# sensor.net
KiCad netlist of a schematic drawn in Altium Designer
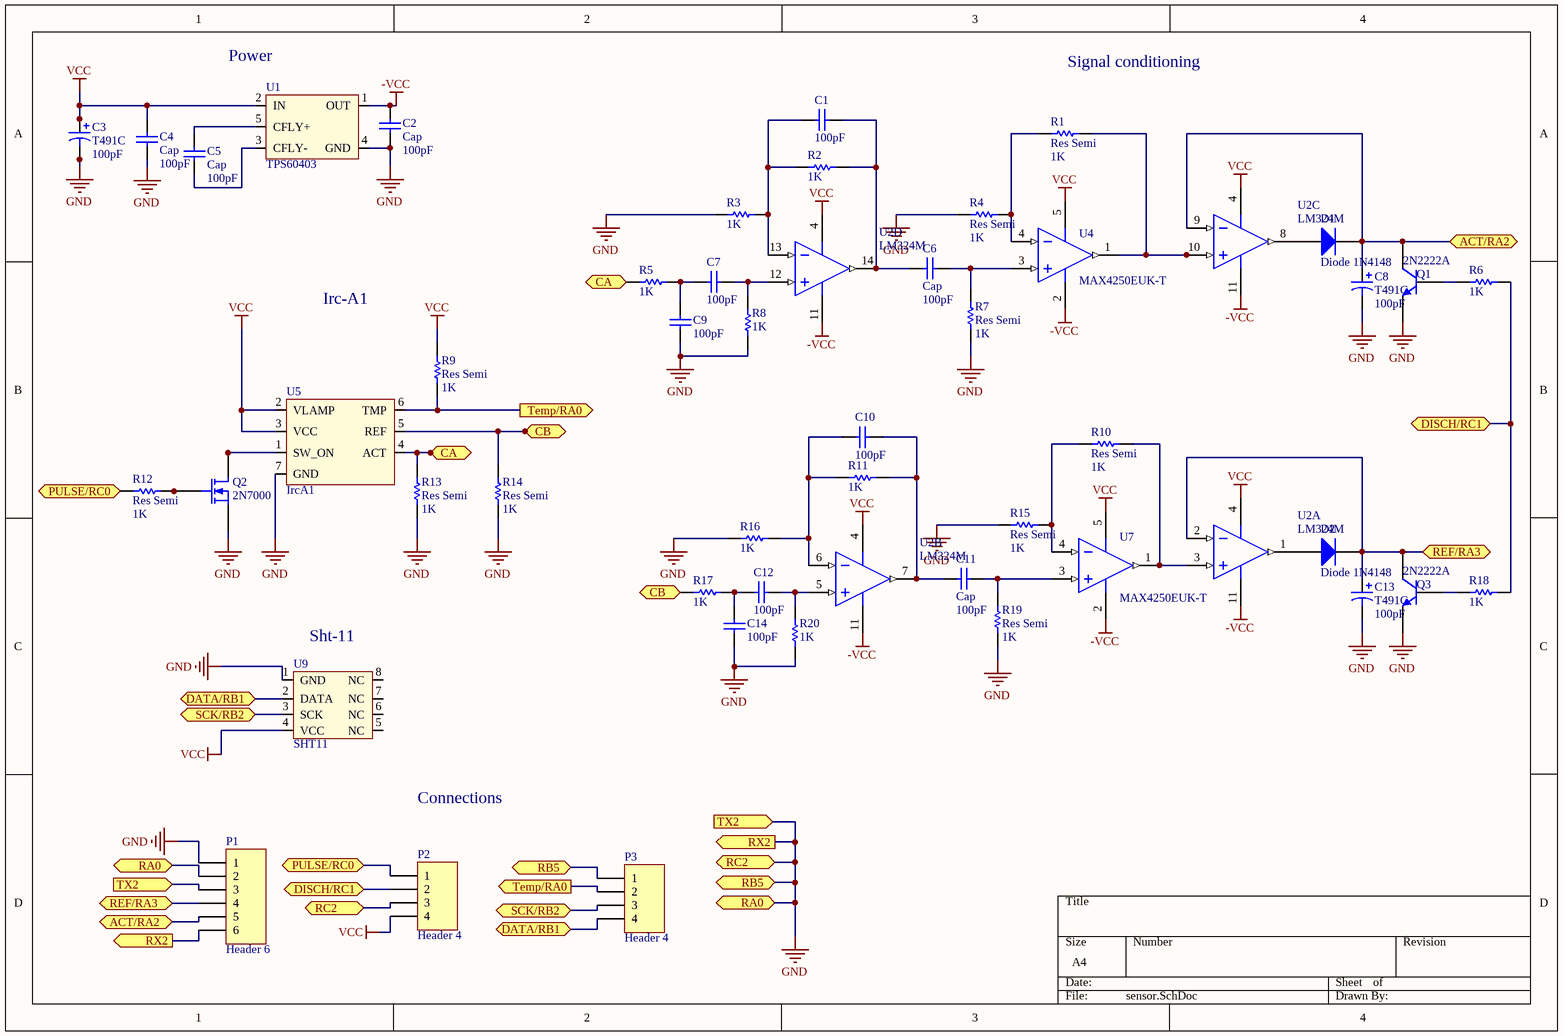
[diagram p0: sensor.SchDoc]

(export (version "E")
  (design (tool "Eeschema 10.0.6"))
  (components
    (comp (ref "C1")
      (value "100pF")
      (footprint "C1206")
      (description "Capacitor")
      (fields (field (name "Comment") "Cap") (field (name "PUBLISHER") "Altium Limited"))
      (libsource (lib "Miscellaneous Devices") (part "Cap"))
    )
    (comp (ref "C2")
      (value "Cap")
      (footprint "C1206")
      (description "Capacitor")
      (fields (field (name "ALTIUM_VALUE") "100pF") (field (name "PUBLISHER") "Altium Limited"))
      (libsource (lib "Miscellaneous Devices") (part "Cap"))
    )
    (comp (ref "C3")
      (value "T491C")
      (footprint "C")
      (description "Solid Tantalum Chip Capacitor, Standard T491 Series - Industrial Grade")
      (fields (field (name "ALTIUM_VALUE") "100pF") (field (name "PUBLISHER") "Altium Limited"))
      (libsource (lib "KEMET Chip Capacitor") (part "T491C"))
    )
    (comp (ref "C4")
      (value "Cap")
      (footprint "C1206")
      (description "Capacitor")
      (fields (field (name "ALTIUM_VALUE") "100pF") (field (name "PUBLISHER") "Altium Limited"))
      (libsource (lib "Miscellaneous Devices") (part "Cap"))
    )
    (comp (ref "C5")
      (value "Cap")
      (footprint "C1206")
      (description "Capacitor")
      (fields (field (name "ALTIUM_VALUE") "100pF") (field (name "PUBLISHER") "Altium Limited"))
      (libsource (lib "Miscellaneous Devices") (part "Cap"))
    )
    (comp (ref "C6")
      (value "Cap")
      (footprint "C1206")
      (description "Capacitor")
      (fields (field (name "ALTIUM_VALUE") "100pF") (field (name "PUBLISHER") "Altium Limited"))
      (libsource (lib "Miscellaneous Devices") (part "Cap"))
    )
    (comp (ref "C7")
      (value "100pF")
      (footprint "C1206")
      (description "Capacitor")
      (fields (field (name "Comment") "Cap") (field (name "PUBLISHER") "Altium Limited"))
      (libsource (lib "Miscellaneous Devices") (part "Cap"))
    )
    (comp (ref "C8")
      (value "T491C")
      (footprint "C")
      (description "Solid Tantalum Chip Capacitor, Standard T491 Series - Industrial Grade")
      (fields (field (name "ALTIUM_VALUE") "100pF") (field (name "PUBLISHER") "Altium Limited"))
      (libsource (lib "KEMET Chip Capacitor") (part "T491C"))
    )
    (comp (ref "C9")
      (value "100pF")
      (footprint "C1206")
      (description "Capacitor")
      (fields (field (name "Comment") "Cap") (field (name "PUBLISHER") "Altium Limited"))
      (libsource (lib "Miscellaneous Devices") (part "Cap"))
    )
    (comp (ref "C10")
      (value "100pF")
      (footprint "C1206")
      (description "Capacitor")
      (fields (field (name "Comment") "Cap") (field (name "PUBLISHER") "Altium Limited"))
      (libsource (lib "Miscellaneous Devices") (part "Cap"))
    )
    (comp (ref "C11")
      (value "Cap")
      (footprint "C1206")
      (description "Capacitor")
      (fields (field (name "ALTIUM_VALUE") "100pF") (field (name "PUBLISHER") "Altium Limited"))
      (libsource (lib "Miscellaneous Devices") (part "Cap"))
    )
    (comp (ref "C12")
      (value "100pF")
      (footprint "C1206")
      (description "Capacitor")
      (fields (field (name "Comment") "Cap") (field (name "PUBLISHER") "Altium Limited"))
      (libsource (lib "Miscellaneous Devices") (part "Cap"))
    )
    (comp (ref "C13")
      (value "T491C")
      (footprint "C")
      (description "Solid Tantalum Chip Capacitor, Standard T491 Series - Industrial Grade")
      (fields (field (name "ALTIUM_VALUE") "100pF") (field (name "PUBLISHER") "Altium Limited"))
      (libsource (lib "KEMET Chip Capacitor") (part "T491C"))
    )
    (comp (ref "C14")
      (value "100pF")
      (footprint "C1206")
      (description "Capacitor")
      (fields (field (name "Comment") "Cap") (field (name "PUBLISHER") "Altium Limited"))
      (libsource (lib "Miscellaneous Devices") (part "Cap"))
    )
    (comp (ref "D1")
      (value "Diode 1N4148")
      (footprint "LED SMD 1206")
      (description "High Conductance Fast Diode")
      (fields (field (name "PUBLISHER") "Altium Limited"))
      (libsource (lib "Miscellaneous Devices") (part "Diode 1N4148"))
    )
    (comp (ref "D2")
      (value "Diode 1N4148")
      (footprint "LED SMD 1206")
      (description "High Conductance Fast Diode")
      (fields (field (name "PUBLISHER") "Altium Limited"))
      (libsource (lib "Miscellaneous Devices") (part "Diode 1N4148"))
    )
    (comp (ref "P1")
      (value "Header 6")
      (footprint "HDR1X6")
      (description "Header, 6-Pin")
      (fields (field (name "PUBLISHER") "Altium Limited"))
      (libsource (lib "Miscellaneous Connectors") (part "Header 6"))
    )
    (comp (ref "P2")
      (value "Header 4")
      (footprint "HDR1X4")
      (description "Header, 4-Pin")
      (fields (field (name "PUBLISHER") "Altium Limited"))
      (libsource (lib "Miscellaneous Connectors") (part "Header 4"))
    )
    (comp (ref "P3")
      (value "Header 4")
      (footprint "HDR1X4")
      (description "Header, 4-Pin")
      (fields (field (name "PUBLISHER") "Altium Limited"))
      (libsource (lib "Miscellaneous Connectors") (part "Header 4"))
    )
    (comp (ref "Q1")
      (value "2N2222A")
      (footprint "SOT323-3BM")
      (description "High Speed Switches")
      (fields (field (name "PUBLISHER") "Altium Limited"))
      (libsource (lib "ST Discrete BJT") (part "2N2222A"))
    )
    (comp (ref "Q2")
      (value "2N7000")
      (footprint "SOT23-3L")
      (description "N-Channel Enhancement Mode Vertical DMOS FET")
      (fields (field (name "PUBLISHER") "Altium Limited"))
      (libsource (lib "Zetex Discrete MOSFET") (part "2N7000"))
    )
    (comp (ref "Q3")
      (value "2N2222A")
      (footprint "SOT323-3BM")
      (description "High Speed Switches")
      (fields (field (name "PUBLISHER") "Altium Limited"))
      (libsource (lib "ST Discrete BJT") (part "2N2222A"))
    )
    (comp (ref "R1")
      (value "Res Semi")
      (footprint "3216[1206]")
      (description "Semiconductor Resistor")
      (fields (field (name "ALTIUM_VALUE") "1K") (field (name "PUBLISHER") "Altium Limited"))
      (libsource (lib "Miscellaneous Devices") (part "Res Semi"))
    )
    (comp (ref "R2")
      (value "1K")
      (footprint "3216[1206]")
      (description "Semiconductor Resistor")
      (fields (field (name "Comment") "Res Semi") (field (name "PUBLISHER") "Altium Limited"))
      (libsource (lib "Miscellaneous Devices") (part "Res Semi"))
    )
    (comp (ref "R3")
      (value "1K")
      (footprint "3216[1206]")
      (description "Semiconductor Resistor")
      (fields (field (name "Comment") "Res Semi") (field (name "PUBLISHER") "Altium Limited"))
      (libsource (lib "Miscellaneous Devices") (part "Res Semi"))
    )
    (comp (ref "R4")
      (value "Res Semi")
      (footprint "3216[1206]")
      (description "Semiconductor Resistor")
      (fields (field (name "ALTIUM_VALUE") "1K") (field (name "PUBLISHER") "Altium Limited"))
      (libsource (lib "Miscellaneous Devices") (part "Res Semi"))
    )
    (comp (ref "R5")
      (value "1K")
      (footprint "3216[1206]")
      (description "Semiconductor Resistor")
      (fields (field (name "Comment") "Res Semi") (field (name "PUBLISHER") "Altium Limited"))
      (libsource (lib "Miscellaneous Devices") (part "Res Semi"))
    )
    (comp (ref "R6")
      (value "1K")
      (footprint "3216[1206]")
      (description "Semiconductor Resistor")
      (fields (field (name "Comment") "Res Semi") (field (name "PUBLISHER") "Altium Limited"))
      (libsource (lib "Miscellaneous Devices") (part "Res Semi"))
    )
    (comp (ref "R7")
      (value "Res Semi")
      (footprint "3216[1206]")
      (description "Semiconductor Resistor")
      (fields (field (name "ALTIUM_VALUE") "1K") (field (name "PUBLISHER") "Altium Limited"))
      (libsource (lib "Miscellaneous Devices") (part "Res Semi"))
    )
    (comp (ref "R8")
      (value "1K")
      (footprint "3216[1206]")
      (description "Semiconductor Resistor")
      (fields (field (name "Comment") "Res Semi") (field (name "PUBLISHER") "Altium Limited"))
      (libsource (lib "Miscellaneous Devices") (part "Res Semi"))
    )
    (comp (ref "R9")
      (value "Res Semi")
      (footprint "3216[1206]")
      (description "Semiconductor Resistor")
      (fields (field (name "ALTIUM_VALUE") "1K") (field (name "PUBLISHER") "Altium Limited"))
      (libsource (lib "Miscellaneous Devices") (part "Res Semi"))
    )
    (comp (ref "R10")
      (value "Res Semi")
      (footprint "3216[1206]")
      (description "Semiconductor Resistor")
      (fields (field (name "ALTIUM_VALUE") "1K") (field (name "PUBLISHER") "Altium Limited"))
      (libsource (lib "Miscellaneous Devices") (part "Res Semi"))
    )
    (comp (ref "R11")
      (value "1K")
      (footprint "3216[1206]")
      (description "Semiconductor Resistor")
      (fields (field (name "Comment") "Res Semi") (field (name "PUBLISHER") "Altium Limited"))
      (libsource (lib "Miscellaneous Devices") (part "Res Semi"))
    )
    (comp (ref "R12")
      (value "Res Semi")
      (footprint "3216[1206]")
      (description "Semiconductor Resistor")
      (fields (field (name "ALTIUM_VALUE") "1K") (field (name "PUBLISHER") "Altium Limited"))
      (libsource (lib "Miscellaneous Devices") (part "Res Semi"))
    )
    (comp (ref "R13")
      (value "Res Semi")
      (footprint "3216[1206]")
      (description "Semiconductor Resistor")
      (fields (field (name "ALTIUM_VALUE") "1K") (field (name "PUBLISHER") "Altium Limited"))
      (libsource (lib "Miscellaneous Devices") (part "Res Semi"))
    )
    (comp (ref "R14")
      (value "Res Semi")
      (footprint "3216[1206]")
      (description "Semiconductor Resistor")
      (fields (field (name "ALTIUM_VALUE") "1K") (field (name "PUBLISHER") "Altium Limited"))
      (libsource (lib "Miscellaneous Devices") (part "Res Semi"))
    )
    (comp (ref "R15")
      (value "Res Semi")
      (footprint "3216[1206]")
      (description "Semiconductor Resistor")
      (fields (field (name "ALTIUM_VALUE") "1K") (field (name "PUBLISHER") "Altium Limited"))
      (libsource (lib "Miscellaneous Devices") (part "Res Semi"))
    )
    (comp (ref "R16")
      (value "1K")
      (footprint "3216[1206]")
      (description "Semiconductor Resistor")
      (fields (field (name "Comment") "Res Semi") (field (name "PUBLISHER") "Altium Limited"))
      (libsource (lib "Miscellaneous Devices") (part "Res Semi"))
    )
    (comp (ref "R17")
      (value "1K")
      (footprint "3216[1206]")
      (description "Semiconductor Resistor")
      (fields (field (name "Comment") "Res Semi") (field (name "PUBLISHER") "Altium Limited"))
      (libsource (lib "Miscellaneous Devices") (part "Res Semi"))
    )
    (comp (ref "R18")
      (value "1K")
      (footprint "3216[1206]")
      (description "Semiconductor Resistor")
      (fields (field (name "Comment") "Res Semi") (field (name "PUBLISHER") "Altium Limited"))
      (libsource (lib "Miscellaneous Devices") (part "Res Semi"))
    )
    (comp (ref "R19")
      (value "Res Semi")
      (footprint "3216[1206]")
      (description "Semiconductor Resistor")
      (fields (field (name "ALTIUM_VALUE") "1K") (field (name "PUBLISHER") "Altium Limited"))
      (libsource (lib "Miscellaneous Devices") (part "Res Semi"))
    )
    (comp (ref "R20")
      (value "1K")
      (footprint "3216[1206]")
      (description "Semiconductor Resistor")
      (fields (field (name "Comment") "Res Semi") (field (name "PUBLISHER") "Altium Limited"))
      (libsource (lib "Miscellaneous Devices") (part "Res Semi"))
    )
    (comp (ref "U1") (value "TPS60403") (footprint "SOT23-5AL") (libsource (lib "uMote") (part "TPS60403")))
    (comp (ref "U2")
      (value "LM324M")
      (footprint "M14A_M")
      (description "Low Power Quad Operational Amplifier")
      (fields
        (field (name "MANUFACTURER") "National Semiconductor")
        (field (name "DIGIKEYPARTNUMBER") "LM324MXCT-ND")
        (field (name "PUBLISHER") "Altium Limited")
      )
      (libsource (lib "NSC Amplifier") (part "LM324M"))
    )
    (comp (ref "U4")
      (value "MAX4250EUK-T")
      (footprint "SOT23-5AM")
      (description "SOT23, Single-Supply, Low-Noise, Low-Distortion, Rail-to-Rail Op Amp")
      (fields (field (name "PUBLISHER") "Altium Limited"))
      (libsource (lib "Maxim Operational Amplifier") (part "MAX4250EUK-T"))
    )
    (comp (ref "U5") (value "IrcA1") (footprint "IrcA1") (libsource (lib "uMote") (part "IrcA1")))
    (comp (ref "U7")
      (value "MAX4250EUK-T")
      (footprint "SOT23-5AM")
      (description "SOT23, Single-Supply, Low-Noise, Low-Distortion, Rail-to-Rail Op Amp")
      (fields (field (name "PUBLISHER") "Altium Limited"))
      (libsource (lib "Maxim Operational Amplifier") (part "MAX4250EUK-T"))
    )
    (comp (ref "U9") (value "SHT11") (footprint "SHT11") (libsource (lib "uMote") (part "SHT11")))
  )
  (nets
    (net (code "1") (name "-VCC") (class "Default")
      (node (ref "C2") (pin "2") (pinfunction "2_2") (pintype "passive"))
      (node (ref "U1") (pin "1") (pinfunction "OUT_1") (pintype "passive"))
      (node (ref "U2") (pin "11") (pinfunction "GND_11") (pintype "power_in"))
      (node (ref "U4") (pin "2") (pinfunction "VSS_2") (pintype "power_in"))
      (node (ref "U7") (pin "2") (pinfunction "VSS_2") (pintype "power_in"))
    )
    (net (code "2") (name "/ACT{slash}RA2") (class "Default")
      (node (ref "C8") (pin "1") (pinfunction "1_1") (pintype "passive"))
      (node (ref "D1") (pin "2") (pinfunction "K_2") (pintype "passive"))
      (node (ref "P1") (pin "5") (pinfunction "5_5") (pintype "passive"))
      (node (ref "Q1") (pin "2") (pinfunction "C_2") (pintype "passive"))
      (node (ref "U2") (pin "9") (pinfunction "IN3-_9") (pintype "input"))
    )
    (net (code "3") (name "/CA") (class "Default")
      (node (ref "R13") (pin "1") (pinfunction "1_1") (pintype "passive"))
      (node (ref "R5") (pin "2") (pinfunction "2_2") (pintype "passive"))
      (node (ref "U5") (pin "4") (pinfunction "ACT_4") (pintype "passive"))
    )
    (net (code "4") (name "/CB") (class "Default")
      (node (ref "R14") (pin "1") (pinfunction "1_1") (pintype "passive"))
      (node (ref "R17") (pin "2") (pinfunction "2_2") (pintype "passive"))
      (node (ref "U5") (pin "5") (pinfunction "REF_5") (pintype "passive"))
    )
    (net (code "5") (name "/DATA{slash}RB1") (class "Default")
      (node (ref "P3") (pin "4") (pinfunction "4_4") (pintype "passive"))
      (node (ref "U9") (pin "2") (pinfunction "DATA_2") (pintype "passive"))
    )
    (net (code "6") (name "/DISCH{slash}RC1") (class "Default")
      (node (ref "P2") (pin "2") (pinfunction "2_2") (pintype "passive"))
      (node (ref "R18") (pin "2") (pinfunction "2_2") (pintype "passive"))
      (node (ref "R6") (pin "2") (pinfunction "2_2") (pintype "passive"))
    )
    (net (code "7") (name "/PULSE{slash}RC0") (class "Default")
      (node (ref "P2") (pin "1") (pinfunction "1_1") (pintype "passive"))
      (node (ref "R12") (pin "1") (pinfunction "1_1") (pintype "passive"))
    )
    (net (code "8") (name "/REF{slash}RA3") (class "Default")
      (node (ref "C13") (pin "1") (pinfunction "1_1") (pintype "passive"))
      (node (ref "D2") (pin "2") (pinfunction "K_2") (pintype "passive"))
      (node (ref "P1") (pin "4") (pinfunction "4_4") (pintype "passive"))
      (node (ref "Q3") (pin "2") (pinfunction "C_2") (pintype "passive"))
      (node (ref "U2") (pin "2") (pinfunction "IN1-_2") (pintype "input"))
    )
    (net (code "9") (name "/SCK{slash}RB2") (class "Default")
      (node (ref "P3") (pin "3") (pinfunction "3_3") (pintype "passive"))
      (node (ref "U9") (pin "3") (pinfunction "SCK_3") (pintype "passive"))
    )
    (net (code "10") (name "/Temp{slash}RA0") (class "Default")
      (node (ref "P3") (pin "2") (pinfunction "2_2") (pintype "passive"))
      (node (ref "R9") (pin "1") (pinfunction "1_1") (pintype "passive"))
      (node (ref "U5") (pin "6") (pinfunction "TMP_6") (pintype "passive"))
    )
    (net (code "11") (name "GND") (class "Default")
      (node (ref "C13") (pin "2") (pinfunction "2_2") (pintype "passive"))
      (node (ref "C14") (pin "1") (pinfunction "1_1") (pintype "passive"))
      (node (ref "C2") (pin "1") (pinfunction "1_1") (pintype "passive"))
      (node (ref "C3") (pin "2") (pinfunction "2_2") (pintype "passive"))
      (node (ref "C4") (pin "2") (pinfunction "2_2") (pintype "passive"))
      (node (ref "C8") (pin "2") (pinfunction "2_2") (pintype "passive"))
      (node (ref "C9") (pin "1") (pinfunction "1_1") (pintype "passive"))
      (node (ref "P1") (pin "1") (pinfunction "1_1") (pintype "passive"))
      (node (ref "P1") (pin "2") (pinfunction "2_2") (pintype "passive"))
      (node (ref "P1") (pin "3") (pinfunction "3_3") (pintype "passive"))
      (node (ref "P1") (pin "6") (pinfunction "6_6") (pintype "passive"))
      (node (ref "P2") (pin "3") (pinfunction "3_3") (pintype "passive"))
      (node (ref "P3") (pin "1") (pinfunction "1_1") (pintype "passive"))
      (node (ref "Q1") (pin "3") (pinfunction "E_3") (pintype "passive"))
      (node (ref "Q2") (pin "1") (pinfunction "S_1") (pintype "passive"))
      (node (ref "Q3") (pin "3") (pinfunction "E_3") (pintype "passive"))
      (node (ref "R13") (pin "2") (pinfunction "2_2") (pintype "passive"))
      (node (ref "R14") (pin "2") (pinfunction "2_2") (pintype "passive"))
      (node (ref "R15") (pin "2") (pinfunction "2_2") (pintype "passive"))
      (node (ref "R16") (pin "1") (pinfunction "1_1") (pintype "passive"))
      (node (ref "R19") (pin "1") (pinfunction "1_1") (pintype "passive"))
      (node (ref "R20") (pin "1") (pinfunction "1_1") (pintype "passive"))
      (node (ref "R3") (pin "1") (pinfunction "1_1") (pintype "passive"))
      (node (ref "R4") (pin "2") (pinfunction "2_2") (pintype "passive"))
      (node (ref "R7") (pin "1") (pinfunction "1_1") (pintype "passive"))
      (node (ref "R8") (pin "1") (pinfunction "1_1") (pintype "passive"))
      (node (ref "U1") (pin "4") (pinfunction "GND_4") (pintype "passive"))
      (node (ref "U5") (pin "7") (pinfunction "GND_7") (pintype "passive"))
      (node (ref "U9") (pin "1") (pinfunction "GND_1") (pintype "passive"))
    )
    (net (code "12") (name "Net-(C7-Pad1)") (class "Default")
      (node (ref "C7") (pin "1") (pinfunction "1_1") (pintype "passive"))
      (node (ref "C9") (pin "2") (pinfunction "2_2") (pintype "passive"))
      (node (ref "R5") (pin "1") (pinfunction "1_1") (pintype "passive"))
    )
    (net (code "13") (name "Net-(C12-Pad1)") (class "Default")
      (node (ref "C12") (pin "1") (pinfunction "1_1") (pintype "passive"))
      (node (ref "C14") (pin "2") (pinfunction "2_2") (pintype "passive"))
      (node (ref "R17") (pin "1") (pinfunction "1_1") (pintype "passive"))
    )
    (net (code "14") (name "Net-(D1-A)") (class "Default")
      (node (ref "D1") (pin "1") (pinfunction "A_1") (pintype "passive"))
      (node (ref "U2") (pin "8") (pinfunction "OUT3_8") (pintype "output"))
    )
    (net (code "15") (name "Net-(D2-A)") (class "Default")
      (node (ref "D2") (pin "1") (pinfunction "A_1") (pintype "passive"))
      (node (ref "U2") (pin "1") (pinfunction "OUT1_1") (pintype "output"))
    )
    (net (code "16") (name "Net-(Q1-B)") (class "Default")
      (node (ref "Q1") (pin "1") (pinfunction "B_1") (pintype "passive"))
      (node (ref "R6") (pin "1") (pinfunction "1_1") (pintype "passive"))
    )
    (net (code "17") (name "Net-(Q2-D)") (class "Default")
      (node (ref "Q2") (pin "3") (pinfunction "D_3") (pintype "passive"))
      (node (ref "U5") (pin "1") (pinfunction "SW_ON_1") (pintype "passive"))
    )
    (net (code "18") (name "Net-(Q2-G)") (class "Default")
      (node (ref "Q2") (pin "2") (pinfunction "G_2") (pintype "passive"))
      (node (ref "R12") (pin "2") (pinfunction "2_2") (pintype "passive"))
    )
    (net (code "19") (name "Net-(Q3-B)") (class "Default")
      (node (ref "Q3") (pin "1") (pinfunction "B_1") (pintype "passive"))
      (node (ref "R18") (pin "1") (pinfunction "1_1") (pintype "passive"))
    )
    (net (code "20") (name "Net-(U1-CFLY+)") (class "Default")
      (node (ref "C5") (pin "1") (pinfunction "1_1") (pintype "passive"))
      (node (ref "U1") (pin "5") (pinfunction "CFLY+_5") (pintype "passive"))
    )
    (net (code "21") (name "Net-(U1-CFLY-)") (class "Default")
      (node (ref "C5") (pin "2") (pinfunction "2_2") (pintype "passive"))
      (node (ref "U1") (pin "3") (pinfunction "CFLY-_3") (pintype "passive"))
    )
    (net (code "22") (name "Net-(U2A-IN1+)") (class "Default")
      (node (ref "R10") (pin "1") (pinfunction "1_1") (pintype "passive"))
      (node (ref "U2") (pin "3") (pinfunction "IN1+_3") (pintype "input"))
      (node (ref "U7") (pin "1") (pinfunction "OUT_1") (pintype "output"))
    )
    (net (code "23") (name "Net-(U2B-IN2+)") (class "Default")
      (node (ref "C12") (pin "2") (pinfunction "2_2") (pintype "passive"))
      (node (ref "R20") (pin "2") (pinfunction "2_2") (pintype "passive"))
      (node (ref "U2") (pin "5") (pinfunction "IN2+_5") (pintype "input"))
    )
    (net (code "24") (name "Net-(U2B-IN2-)") (class "Default")
      (node (ref "C10") (pin "1") (pinfunction "1_1") (pintype "passive"))
      (node (ref "R11") (pin "1") (pinfunction "1_1") (pintype "passive"))
      (node (ref "R16") (pin "2") (pinfunction "2_2") (pintype "passive"))
      (node (ref "U2") (pin "6") (pinfunction "IN2-_6") (pintype "input"))
    )
    (net (code "25") (name "Net-(U2B-OUT2)") (class "Default")
      (node (ref "C10") (pin "2") (pinfunction "2_2") (pintype "passive"))
      (node (ref "C11") (pin "1") (pinfunction "1_1") (pintype "passive"))
      (node (ref "R11") (pin "2") (pinfunction "2_2") (pintype "passive"))
      (node (ref "U2") (pin "7") (pinfunction "OUT2_7") (pintype "output"))
    )
    (net (code "26") (name "Net-(U2C-IN3+)") (class "Default")
      (node (ref "R1") (pin "1") (pinfunction "1_1") (pintype "passive"))
      (node (ref "U2") (pin "10") (pinfunction "IN3+_10") (pintype "input"))
      (node (ref "U4") (pin "1") (pinfunction "OUT_1") (pintype "output"))
    )
    (net (code "27") (name "Net-(U2D-IN4+)") (class "Default")
      (node (ref "C7") (pin "2") (pinfunction "2_2") (pintype "passive"))
      (node (ref "R8") (pin "2") (pinfunction "2_2") (pintype "passive"))
      (node (ref "U2") (pin "12") (pinfunction "IN4+_12") (pintype "input"))
    )
    (net (code "28") (name "Net-(U2D-IN4-)") (class "Default")
      (node (ref "C1") (pin "1") (pinfunction "1_1") (pintype "passive"))
      (node (ref "R2") (pin "1") (pinfunction "1_1") (pintype "passive"))
      (node (ref "R3") (pin "2") (pinfunction "2_2") (pintype "passive"))
      (node (ref "U2") (pin "13") (pinfunction "IN4-_13") (pintype "input"))
    )
    (net (code "29") (name "Net-(U2D-OUT4)") (class "Default")
      (node (ref "C1") (pin "2") (pinfunction "2_2") (pintype "passive"))
      (node (ref "C6") (pin "1") (pinfunction "1_1") (pintype "passive"))
      (node (ref "R2") (pin "2") (pinfunction "2_2") (pintype "passive"))
      (node (ref "U2") (pin "14") (pinfunction "OUT4_14") (pintype "output"))
    )
    (net (code "30") (name "Net-(U4-IN+)") (class "Default")
      (node (ref "C6") (pin "2") (pinfunction "2_2") (pintype "passive"))
      (node (ref "R7") (pin "2") (pinfunction "2_2") (pintype "passive"))
      (node (ref "U4") (pin "3") (pinfunction "IN+_3") (pintype "input"))
    )
    (net (code "31") (name "Net-(U4-IN-)") (class "Default")
      (node (ref "R1") (pin "2") (pinfunction "2_2") (pintype "passive"))
      (node (ref "R4") (pin "1") (pinfunction "1_1") (pintype "passive"))
      (node (ref "U4") (pin "4") (pinfunction "IN-_4") (pintype "input"))
    )
    (net (code "32") (name "Net-(U7-IN+)") (class "Default")
      (node (ref "C11") (pin "2") (pinfunction "2_2") (pintype "passive"))
      (node (ref "R19") (pin "2") (pinfunction "2_2") (pintype "passive"))
      (node (ref "U7") (pin "3") (pinfunction "IN+_3") (pintype "input"))
    )
    (net (code "33") (name "Net-(U7-IN-)") (class "Default")
      (node (ref "R10") (pin "2") (pinfunction "2_2") (pintype "passive"))
      (node (ref "R15") (pin "1") (pinfunction "1_1") (pintype "passive"))
      (node (ref "U7") (pin "4") (pinfunction "IN-_4") (pintype "input"))
    )
    (net (code "34") (name "VCC") (class "Default")
      (node (ref "C3") (pin "1") (pinfunction "1_1") (pintype "passive"))
      (node (ref "C4") (pin "1") (pinfunction "1_1") (pintype "passive"))
      (node (ref "P2") (pin "4") (pinfunction "4_4") (pintype "passive"))
      (node (ref "R9") (pin "2") (pinfunction "2_2") (pintype "passive"))
      (node (ref "U1") (pin "2") (pinfunction "IN_2") (pintype "passive"))
      (node (ref "U2") (pin "4") (pinfunction "V+_4") (pintype "power_in"))
      (node (ref "U4") (pin "5") (pinfunction "VDD_5") (pintype "power_in"))
      (node (ref "U5") (pin "2") (pinfunction "VLAMP_2") (pintype "passive"))
      (node (ref "U5") (pin "3") (pinfunction "VCC_3") (pintype "passive"))
      (node (ref "U7") (pin "5") (pinfunction "VDD_5") (pintype "power_in"))
      (node (ref "U9") (pin "4") (pinfunction "VCC_4") (pintype "passive"))
    )
    (net (code "35") (name "unconnected-(U9-NC-Pad5)") (class "Default")
      (node (ref "U9") (pin "5") (pinfunction "NC_5") (pintype "passive"))
    )
    (net (code "36") (name "unconnected-(U9-NC-Pad6)") (class "Default")
      (node (ref "U9") (pin "6") (pinfunction "NC_6") (pintype "passive"))
    )
    (net (code "37") (name "unconnected-(U9-NC-Pad7)") (class "Default")
      (node (ref "U9") (pin "7") (pinfunction "NC_7") (pintype "passive"))
    )
    (net (code "38") (name "unconnected-(U9-NC-Pad8)") (class "Default")
      (node (ref "U9") (pin "8") (pinfunction "NC_8") (pintype "passive"))
    )
  )
)
